# ESP8266-SeeedBreakoutBoardMinimal.net
KiCad netlist of a schematic drawn in EAGLE
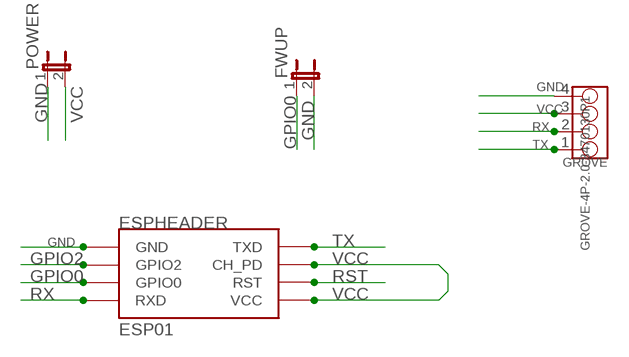
[diagram p0: schematic, sheet 1]

(export (version "E")
  (design (tool "Eeschema 10.0.6"))
  (components
    (comp (ref "ESPHEADER")
      (value "ESP01")
      (footprint "eagle-import:ESP01")
      (libsource (lib "eagle-import") (part "ESP01"))
    )
    (comp (ref "FWUP")
      (value "JUMPER-2PTH")
      (footprint "eagle-import:1X02")
      (libsource (lib "eagle-import") (part "JUMPER-2PTH"))
    )
    (comp (ref "GROVE")
      (value "GROVE-4P-2.0-3470130P1")
      (footprint "eagle-import:4P-2.0")
      (libsource (lib "eagle-import") (part "GROVE-4P-2.0-3470130P1"))
    )
    (comp (ref "POWER")
      (value "JUMPER-2PTH")
      (footprint "eagle-import:1X02")
      (libsource (lib "eagle-import") (part "JUMPER-2PTH"))
    )
  )
  (nets
    (net (code "1") (name "/GND") (class "Default")
      (node (ref "ESPHEADER") (pin "GND") (pinfunction "GND_GND") (pintype "bidirectional"))
      (node (ref "FWUP") (pin "2") (pinfunction "2_2") (pintype "passive"))
      (node (ref "GROVE") (pin "4") (pinfunction "4_4") (pintype "bidirectional"))
      (node (ref "POWER") (pin "1") (pinfunction "1_1") (pintype "passive"))
    )
    (net (code "2") (name "/GPIO0") (class "Default")
      (node (ref "ESPHEADER") (pin "GPIO0") (pinfunction "GPIO0_GPIO0") (pintype "bidirectional"))
      (node (ref "FWUP") (pin "1") (pinfunction "1_1") (pintype "passive"))
    )
    (net (code "3") (name "/GPIO2") (class "Default")
      (node (ref "ESPHEADER") (pin "GPIO2") (pinfunction "GPIO2_GPIO2") (pintype "bidirectional"))
    )
    (net (code "4") (name "/RST") (class "Default")
      (node (ref "ESPHEADER") (pin "RST") (pinfunction "RST_RST") (pintype "bidirectional"))
    )
    (net (code "5") (name "/RX") (class "Default")
      (node (ref "ESPHEADER") (pin "RX") (pinfunction "RXD_RX") (pintype "bidirectional"))
      (node (ref "GROVE") (pin "2") (pinfunction "2_2") (pintype "bidirectional"))
    )
    (net (code "6") (name "/TX") (class "Default")
      (node (ref "ESPHEADER") (pin "TX") (pinfunction "TXD_TX") (pintype "bidirectional"))
      (node (ref "GROVE") (pin "1") (pinfunction "1_1") (pintype "bidirectional"))
    )
    (net (code "7") (name "/VCC") (class "Default")
      (node (ref "ESPHEADER") (pin "CH_PD") (pinfunction "CH_PD_CH_PD") (pintype "bidirectional"))
      (node (ref "ESPHEADER") (pin "VCC") (pinfunction "VCC_VCC") (pintype "bidirectional"))
      (node (ref "GROVE") (pin "3") (pinfunction "3_3") (pintype "bidirectional"))
      (node (ref "POWER") (pin "2") (pinfunction "2_2") (pintype "passive"))
    )
  )
)
